# de0-nano_RMII.net
KiCad netlist of a schematic drawn in EAGLE
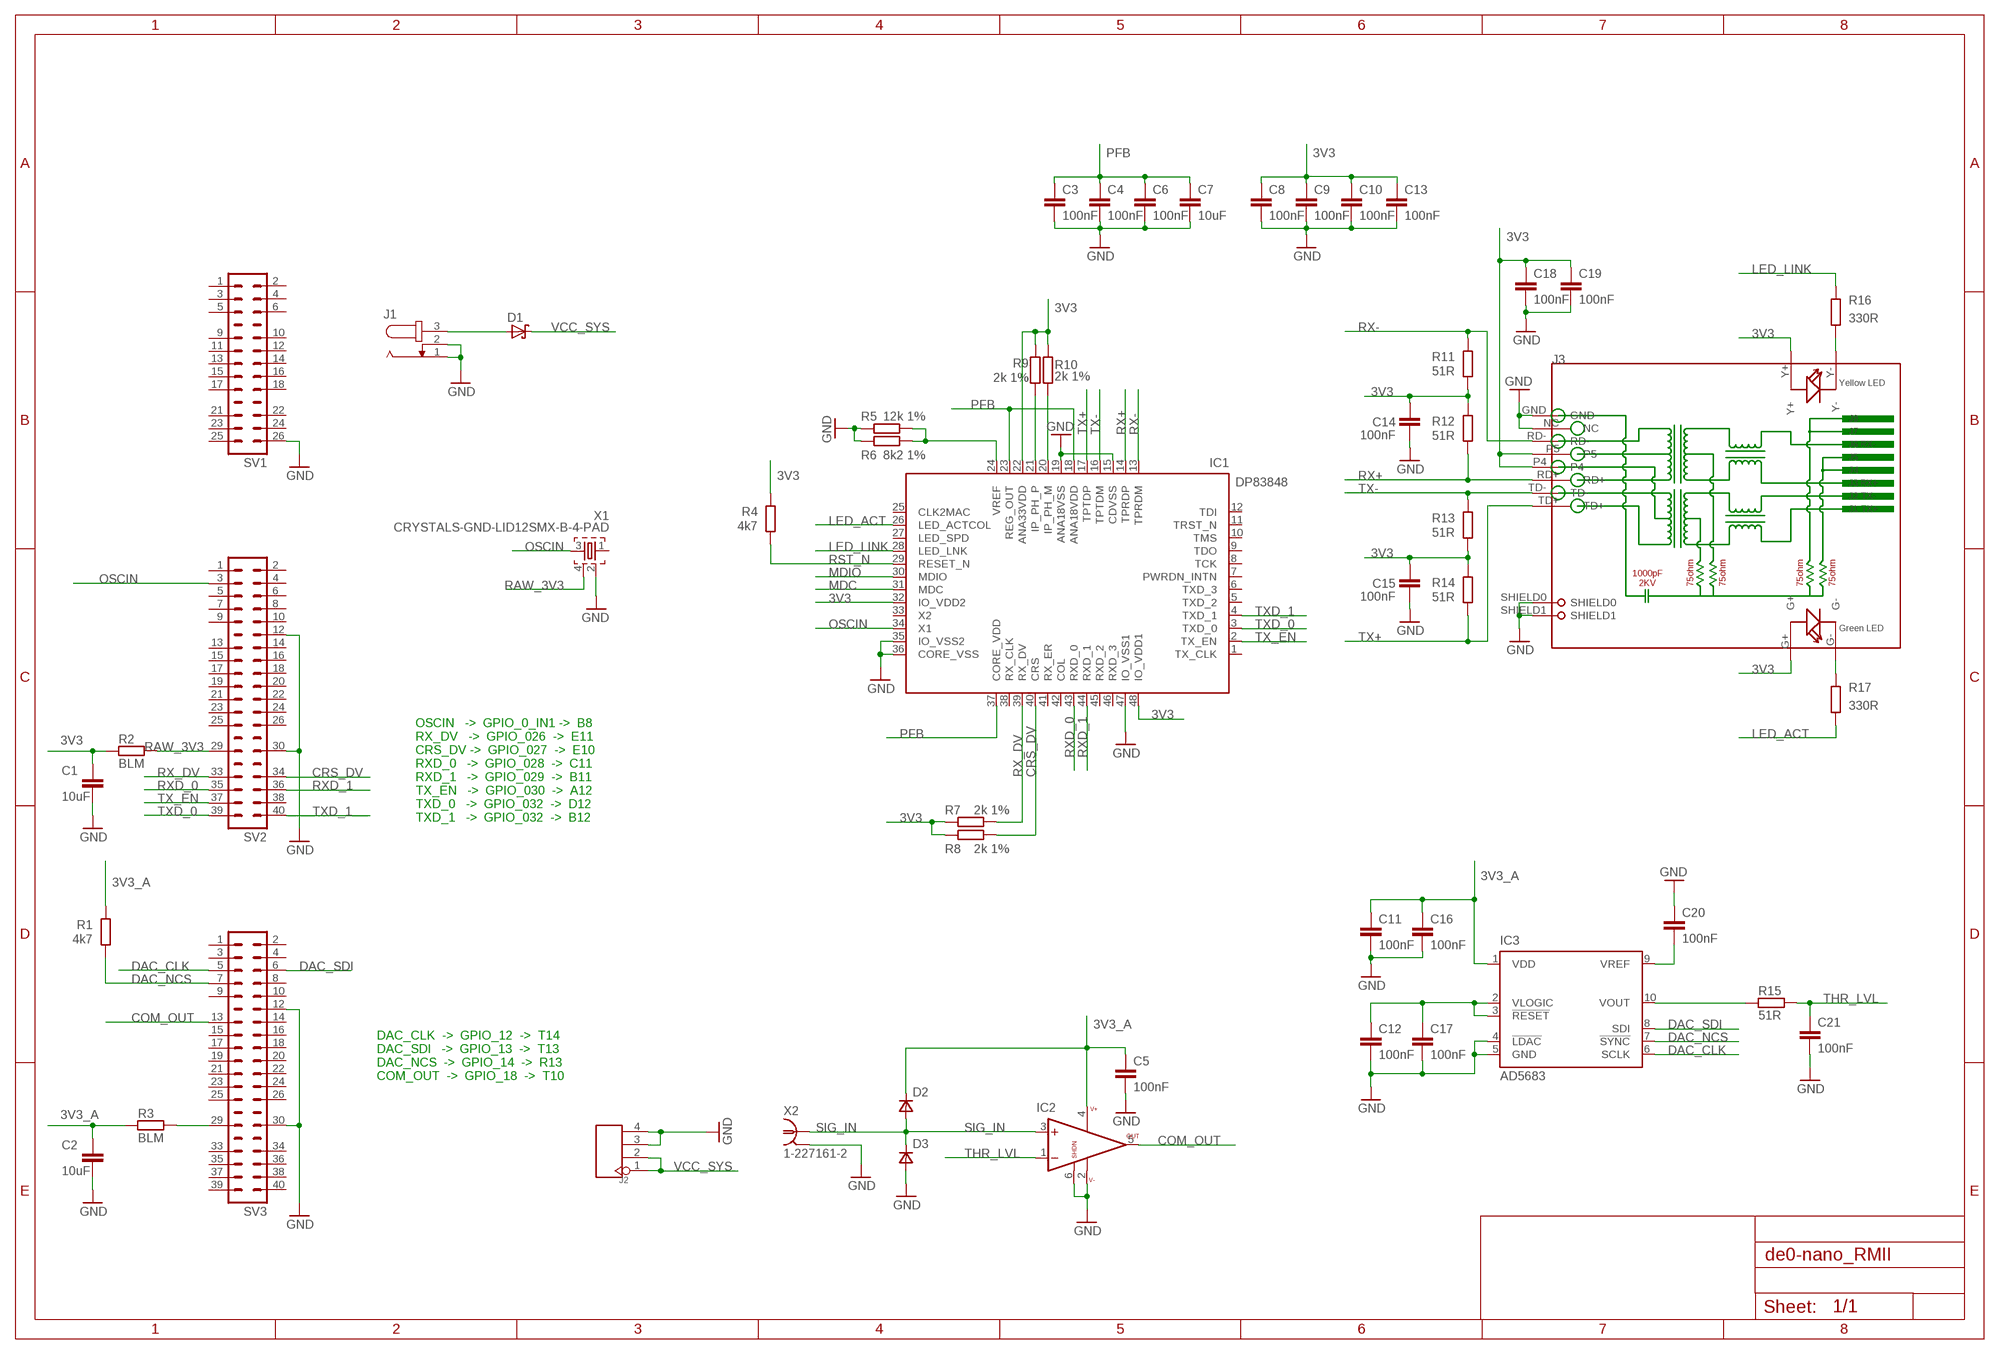
[diagram p0: schematic, sheet 1]

(export (version "E")
  (design (tool "Eeschema 10.0.6"))
  (components
    (comp (ref "C1")
      (value "10uF")
      (footprint "eagle-import:C0805")
      (libsource (lib "eagle-import") (part "C-EUC0805"))
    )
    (comp (ref "C2")
      (value "10uF")
      (footprint "eagle-import:C0805")
      (libsource (lib "eagle-import") (part "C-EUC0805"))
    )
    (comp (ref "C3")
      (value "100nF")
      (footprint "eagle-import:C0603")
      (libsource (lib "eagle-import") (part "C-EUC0603"))
    )
    (comp (ref "C4")
      (value "100nF")
      (footprint "eagle-import:C0603")
      (libsource (lib "eagle-import") (part "C-EUC0603"))
    )
    (comp (ref "C5")
      (value "100nF")
      (footprint "eagle-import:C0603")
      (libsource (lib "eagle-import") (part "C-EUC0603"))
    )
    (comp (ref "C6")
      (value "100nF")
      (footprint "eagle-import:C0603")
      (libsource (lib "eagle-import") (part "C-EUC0603"))
    )
    (comp (ref "C7")
      (value "10uF")
      (footprint "eagle-import:C0805")
      (libsource (lib "eagle-import") (part "C-EUC0805"))
    )
    (comp (ref "C8")
      (value "100nF")
      (footprint "eagle-import:C0603")
      (libsource (lib "eagle-import") (part "C-EUC0603"))
    )
    (comp (ref "C9")
      (value "100nF")
      (footprint "eagle-import:C0603")
      (libsource (lib "eagle-import") (part "C-EUC0603"))
    )
    (comp (ref "C10")
      (value "100nF")
      (footprint "eagle-import:C0603")
      (libsource (lib "eagle-import") (part "C-EUC0603"))
    )
    (comp (ref "C11")
      (value "100nF")
      (footprint "eagle-import:C0603")
      (libsource (lib "eagle-import") (part "C-EUC0603"))
    )
    (comp (ref "C12")
      (value "100nF")
      (footprint "eagle-import:C0603")
      (libsource (lib "eagle-import") (part "C-EUC0603"))
    )
    (comp (ref "C13")
      (value "100nF")
      (footprint "eagle-import:C0603")
      (libsource (lib "eagle-import") (part "C-EUC0603"))
    )
    (comp (ref "C14")
      (value "100nF")
      (footprint "eagle-import:C0603")
      (libsource (lib "eagle-import") (part "C-EUC0603"))
    )
    (comp (ref "C15")
      (value "100nF")
      (footprint "eagle-import:C0603")
      (libsource (lib "eagle-import") (part "C-EUC0603"))
    )
    (comp (ref "C16")
      (value "100nF")
      (footprint "eagle-import:C0603")
      (libsource (lib "eagle-import") (part "C-EUC0603"))
    )
    (comp (ref "C17")
      (value "100nF")
      (footprint "eagle-import:C0603")
      (libsource (lib "eagle-import") (part "C-EUC0603"))
    )
    (comp (ref "C18")
      (value "100nF")
      (footprint "eagle-import:C0603")
      (libsource (lib "eagle-import") (part "C-EUC0603"))
    )
    (comp (ref "C19")
      (value "100nF")
      (footprint "eagle-import:C0603")
      (libsource (lib "eagle-import") (part "C-EUC0603"))
    )
    (comp (ref "C20")
      (value "100nF")
      (footprint "eagle-import:C0603")
      (libsource (lib "eagle-import") (part "C-EUC0603"))
    )
    (comp (ref "C21")
      (value "100nF")
      (footprint "eagle-import:C0603")
      (libsource (lib "eagle-import") (part "C-EUC0603"))
    )
    (comp (ref "D1")
      (value "SCHOTTKY-DIODESMC")
      (footprint "eagle-import:SMC")
      (libsource (lib "eagle-import") (part "SCHOTTKY-DIODESMC"))
    )
    (comp (ref "D2")
      (value "DSOD323")
      (footprint "eagle-import:SOD323")
      (fields (field (name "MPN") "CDSOD323-T05C"))
      (libsource (lib "eagle-import") (part "DSOD323"))
    )
    (comp (ref "D3")
      (value "DSOD323")
      (footprint "eagle-import:SOD323")
      (fields (field (name "MPN") "CDSOD323-T05C"))
      (libsource (lib "eagle-import") (part "DSOD323"))
    )
    (comp (ref "IC1")
      (value "DP83848")
      (footprint "eagle-import:LQFP48")
      (fields (field (name "MPN") "DP83848VYB"))
      (libsource (lib "eagle-import") (part "DP83848"))
    )
    (comp (ref "IC2")
      (value "LT1719")
      (footprint "eagle-import:TSOT23-6")
      (libsource (lib "eagle-import") (part "LT1719"))
    )
    (comp (ref "IC3")
      (value "AD5683")
      (footprint "eagle-import:SO10")
      (fields (field (name "MPN") "SSM2167Z-EVAL"))
      (libsource (lib "eagle-import") (part "AD5683"))
    )
    (comp (ref "J1")
      (value "JACK-PLUG1")
      (footprint "eagle-import:SPC4078")
      (libsource (lib "eagle-import") (part "JACK-PLUG1"))
    )
    (comp (ref "J2")
      (value "HEADER-4P-60/35MIL")
      (footprint "eagle-import:4P-65_35MIL")
      (libsource (lib "eagle-import") (part "HEADER-4P-60/35MIL"))
    )
    (comp (ref "J3")
      (value "RJ45-HR911105A-HR911105A")
      (footprint "eagle-import:RJ45")
      (libsource (lib "eagle-import") (part "RJ45-HR911105A-HR911105A"))
    )
    (comp (ref "R1")
      (value "4k7")
      (footprint "eagle-import:R0603")
      (libsource (lib "eagle-import") (part "R-EU_R0603"))
    )
    (comp (ref "R2")
      (value "BLM")
      (footprint "eagle-import:R0603")
      (libsource (lib "eagle-import") (part "R-EU_R0603"))
    )
    (comp (ref "R3")
      (value "BLM")
      (footprint "eagle-import:R0603")
      (libsource (lib "eagle-import") (part "R-EU_R0603"))
    )
    (comp (ref "R4")
      (value "4k7")
      (footprint "eagle-import:R0603")
      (libsource (lib "eagle-import") (part "R-EU_R0603"))
    )
    (comp (ref "R5")
      (value "12k 1%")
      (footprint "eagle-import:R0603")
      (libsource (lib "eagle-import") (part "R-EU_R0603"))
    )
    (comp (ref "R6")
      (value "8k2 1%")
      (footprint "eagle-import:R0603")
      (libsource (lib "eagle-import") (part "R-EU_R0603"))
    )
    (comp (ref "R7")
      (value "2k 1%")
      (footprint "eagle-import:R0603")
      (libsource (lib "eagle-import") (part "R-EU_R0603"))
    )
    (comp (ref "R8")
      (value "2k 1%")
      (footprint "eagle-import:R0603")
      (libsource (lib "eagle-import") (part "R-EU_R0603"))
    )
    (comp (ref "R9")
      (value "2k 1%")
      (footprint "eagle-import:R0603")
      (libsource (lib "eagle-import") (part "R-EU_R0603"))
    )
    (comp (ref "R10")
      (value "2k 1%")
      (footprint "eagle-import:R0603")
      (libsource (lib "eagle-import") (part "R-EU_R0603"))
    )
    (comp (ref "R11")
      (value "51R")
      (footprint "eagle-import:R0603")
      (libsource (lib "eagle-import") (part "R-EU_R0603"))
    )
    (comp (ref "R12")
      (value "51R")
      (footprint "eagle-import:R0603")
      (libsource (lib "eagle-import") (part "R-EU_R0603"))
    )
    (comp (ref "R13")
      (value "51R")
      (footprint "eagle-import:R0603")
      (libsource (lib "eagle-import") (part "R-EU_R0603"))
    )
    (comp (ref "R14")
      (value "51R")
      (footprint "eagle-import:R0603")
      (libsource (lib "eagle-import") (part "R-EU_R0603"))
    )
    (comp (ref "R15")
      (value "51R")
      (footprint "eagle-import:R0603")
      (libsource (lib "eagle-import") (part "R-EU_R0603"))
    )
    (comp (ref "R16")
      (value "330R")
      (footprint "eagle-import:R0603")
      (libsource (lib "eagle-import") (part "R-EU_R0603"))
    )
    (comp (ref "R17")
      (value "330R")
      (footprint "eagle-import:R0603")
      (libsource (lib "eagle-import") (part "R-EU_R0603"))
    )
    (comp (ref "SV1")
      (value "MA13-2_ALT")
      (footprint "eagle-import:MA13-2_ALT")
      (libsource (lib "eagle-import") (part "MA13-2_ALT"))
    )
    (comp (ref "SV2")
      (value "MA20-2_ALT")
      (footprint "eagle-import:MA20-2_ALT")
      (libsource (lib "eagle-import") (part "MA20-2_ALT"))
    )
    (comp (ref "SV3")
      (value "MA20-2_ALT")
      (footprint "eagle-import:MA20-2_ALT")
      (libsource (lib "eagle-import") (part "MA20-2_ALT"))
    )
    (comp (ref "X1")
      (value "CRYSTALS-GND-LID12SMX-B-4-PAD")
      (footprint "eagle-import:7.5X5-4-PAD")
      (libsource (lib "eagle-import") (part "CRYSTALS-GND-LID-4-PAD12SMX-B"))
    )
    (comp (ref "X2")
      (value "1-227161-2")
      (footprint "eagle-import:AMP_227161")
      (libsource (lib "eagle-import") (part "?2271611--2"))
    )
  )
  (nets
    (net (code "1") (name "/3V3") (class "Default")
      (node (ref "C1") (pin "1") (pinfunction "1_1") (pintype "passive"))
      (node (ref "C10") (pin "1") (pinfunction "1_1") (pintype "passive"))
      (node (ref "C13") (pin "1") (pinfunction "1_1") (pintype "passive"))
      (node (ref "C14") (pin "1") (pinfunction "1_1") (pintype "passive"))
      (node (ref "C15") (pin "1") (pinfunction "1_1") (pintype "passive"))
      (node (ref "C18") (pin "1") (pinfunction "1_1") (pintype "passive"))
      (node (ref "C19") (pin "1") (pinfunction "1_1") (pintype "passive"))
      (node (ref "C8") (pin "1") (pinfunction "1_1") (pintype "passive"))
      (node (ref "C9") (pin "1") (pinfunction "1_1") (pintype "passive"))
      (node (ref "IC1") (pin "22") (pinfunction "ANA33VDD_22") (pintype "power_in"))
      (node (ref "IC1") (pin "32") (pinfunction "IO_VDD2_32") (pintype "power_in"))
      (node (ref "IC1") (pin "48") (pinfunction "IO_VDD1_48") (pintype "power_in"))
      (node (ref "J3") (pin "G+") (pinfunction "G+_G+") (pintype "bidirectional"))
      (node (ref "J3") (pin "P4") (pinfunction "P4_P4") (pintype "bidirectional"))
      (node (ref "J3") (pin "P5") (pinfunction "P5_P5") (pintype "bidirectional"))
      (node (ref "J3") (pin "Y+") (pinfunction "Y+_Y+") (pintype "bidirectional"))
      (node (ref "R10") (pin "2") (pinfunction "2_2") (pintype "passive"))
      (node (ref "R11") (pin "2") (pinfunction "2_2") (pintype "passive"))
      (node (ref "R12") (pin "1") (pinfunction "1_1") (pintype "passive"))
      (node (ref "R13") (pin "2") (pinfunction "2_2") (pintype "passive"))
      (node (ref "R14") (pin "1") (pinfunction "1_1") (pintype "passive"))
      (node (ref "R2") (pin "1") (pinfunction "1_1") (pintype "passive"))
      (node (ref "R4") (pin "1") (pinfunction "1_1") (pintype "passive"))
      (node (ref "R7") (pin "2") (pinfunction "2_2") (pintype "passive"))
      (node (ref "R8") (pin "2") (pinfunction "2_2") (pintype "passive"))
      (node (ref "R9") (pin "2") (pinfunction "2_2") (pintype "passive"))
    )
    (net (code "2") (name "/3V3_A") (class "Default")
      (node (ref "C11") (pin "1") (pinfunction "1_1") (pintype "passive"))
      (node (ref "C16") (pin "1") (pinfunction "1_1") (pintype "passive"))
      (node (ref "C2") (pin "1") (pinfunction "1_1") (pintype "passive"))
      (node (ref "C5") (pin "1") (pinfunction "1_1") (pintype "passive"))
      (node (ref "D2") (pin "1") (pinfunction "C_1") (pintype "passive"))
      (node (ref "IC2") (pin "4") (pinfunction "V+_4") (pintype "power_in"))
      (node (ref "IC3") (pin "1") (pinfunction "VDD_1") (pintype "power_in"))
      (node (ref "R1") (pin "1") (pinfunction "1_1") (pintype "passive"))
      (node (ref "R3") (pin "1") (pinfunction "1_1") (pintype "passive"))
    )
    (net (code "3") (name "/COM_OUT") (class "Default")
      (node (ref "IC2") (pin "5") (pinfunction "OUT_5") (pintype "output"))
      (node (ref "SV3") (pin "13") (pinfunction "13_13") (pintype "passive"))
    )
    (net (code "4") (name "/CRS_DV") (class "Default")
      (node (ref "IC1") (pin "40") (pinfunction "CRS_40") (pintype "bidirectional"))
      (node (ref "R8") (pin "1") (pinfunction "1_1") (pintype "passive"))
      (node (ref "SV2") (pin "34") (pinfunction "34_34") (pintype "passive"))
    )
    (net (code "5") (name "/DAC_CLK") (class "Default")
      (node (ref "IC3") (pin "6") (pinfunction "SCLK_6") (pintype "passive"))
      (node (ref "SV3") (pin "5") (pinfunction "5_5") (pintype "passive"))
    )
    (net (code "6") (name "/DAC_NCS") (class "Default")
      (node (ref "IC3") (pin "7") (pinfunction "~{SYNC}_7") (pintype "passive"))
      (node (ref "R1") (pin "2") (pinfunction "2_2") (pintype "passive"))
      (node (ref "SV3") (pin "7") (pinfunction "7_7") (pintype "passive"))
    )
    (net (code "7") (name "/DAC_SDI") (class "Default")
      (node (ref "IC3") (pin "8") (pinfunction "SDI_8") (pintype "passive"))
      (node (ref "SV3") (pin "6") (pinfunction "6_6") (pintype "passive"))
    )
    (net (code "8") (name "/LED_ACT") (class "Default")
      (node (ref "IC1") (pin "26") (pinfunction "LED_ACTCOL_26") (pintype "bidirectional"))
      (node (ref "R17") (pin "1") (pinfunction "1_1") (pintype "passive"))
    )
    (net (code "9") (name "/LED_LINK") (class "Default")
      (node (ref "IC1") (pin "28") (pinfunction "LED_LNK_28") (pintype "bidirectional"))
      (node (ref "R16") (pin "2") (pinfunction "2_2") (pintype "passive"))
    )
    (net (code "10") (name "/MDC") (class "Default")
      (node (ref "IC1") (pin "31") (pinfunction "MDC_31") (pintype "input"))
    )
    (net (code "11") (name "/MDIO") (class "Default")
      (node (ref "IC1") (pin "30") (pinfunction "MDIO_30") (pintype "bidirectional"))
    )
    (net (code "12") (name "/OSCIN") (class "Default")
      (node (ref "IC1") (pin "34") (pinfunction "X1_34") (pintype "input"))
      (node (ref "SV2") (pin "3") (pinfunction "3_3") (pintype "passive"))
      (node (ref "X1") (pin "3") (pinfunction "3_3") (pintype "passive"))
    )
    (net (code "13") (name "/PFB") (class "Default")
      (node (ref "C3") (pin "1") (pinfunction "1_1") (pintype "passive"))
      (node (ref "C4") (pin "1") (pinfunction "1_1") (pintype "passive"))
      (node (ref "C6") (pin "1") (pinfunction "1_1") (pintype "passive"))
      (node (ref "C7") (pin "1") (pinfunction "1_1") (pintype "passive"))
      (node (ref "IC1") (pin "18") (pinfunction "ANA18VDD_18") (pintype "power_in"))
      (node (ref "IC1") (pin "23") (pinfunction "REG_OUT_23") (pintype "output"))
      (node (ref "IC1") (pin "37") (pinfunction "CORE_VDD_37") (pintype "power_in"))
    )
    (net (code "14") (name "/RAW_3V3") (class "Default")
      (node (ref "R2") (pin "2") (pinfunction "2_2") (pintype "passive"))
      (node (ref "SV2") (pin "29") (pinfunction "29_29") (pintype "passive"))
      (node (ref "X1") (pin "4") (pinfunction "4_4") (pintype "passive"))
    )
    (net (code "15") (name "/RST_N") (class "Default")
      (node (ref "IC1") (pin "29") (pinfunction "RESET_N_29") (pintype "input"))
      (node (ref "R4") (pin "2") (pinfunction "2_2") (pintype "passive"))
    )
    (net (code "16") (name "/RX+") (class "Default")
      (node (ref "IC1") (pin "14") (pinfunction "TPRDP_14") (pintype "bidirectional"))
      (node (ref "J3") (pin "RD+") (pinfunction "RD+_RD+") (pintype "bidirectional"))
      (node (ref "R12") (pin "2") (pinfunction "2_2") (pintype "passive"))
    )
    (net (code "17") (name "/RX-") (class "Default")
      (node (ref "IC1") (pin "13") (pinfunction "TPRDM_13") (pintype "bidirectional"))
      (node (ref "J3") (pin "RD-") (pinfunction "RD-_RD-") (pintype "bidirectional"))
      (node (ref "R11") (pin "1") (pinfunction "1_1") (pintype "passive"))
    )
    (net (code "18") (name "/RXD_0") (class "Default")
      (node (ref "IC1") (pin "43") (pinfunction "RXD_0_43") (pintype "bidirectional"))
      (node (ref "SV2") (pin "35") (pinfunction "35_35") (pintype "passive"))
    )
    (net (code "19") (name "/RXD_1") (class "Default")
      (node (ref "IC1") (pin "44") (pinfunction "RXD_1_44") (pintype "bidirectional"))
      (node (ref "SV2") (pin "36") (pinfunction "36_36") (pintype "passive"))
    )
    (net (code "20") (name "/RX_DV") (class "Default")
      (node (ref "IC1") (pin "39") (pinfunction "RX_DV_39") (pintype "bidirectional"))
      (node (ref "R7") (pin "1") (pinfunction "1_1") (pintype "passive"))
      (node (ref "SV2") (pin "33") (pinfunction "33_33") (pintype "passive"))
    )
    (net (code "21") (name "/SIG_IN") (class "Default")
      (node (ref "D2") (pin "2") (pinfunction "A_2") (pintype "passive"))
      (node (ref "D3") (pin "1") (pinfunction "C_1") (pintype "passive"))
      (node (ref "IC2") (pin "3") (pinfunction "+IN_3") (pintype "input"))
      (node (ref "X2") (pin "1") (pinfunction "1_1") (pintype "passive"))
    )
    (net (code "22") (name "/THR_LVL") (class "Default")
      (node (ref "C21") (pin "1") (pinfunction "1_1") (pintype "passive"))
      (node (ref "IC2") (pin "1") (pinfunction "-IN_1") (pintype "input"))
      (node (ref "R15") (pin "2") (pinfunction "2_2") (pintype "passive"))
    )
    (net (code "23") (name "/TX+") (class "Default")
      (node (ref "IC1") (pin "17") (pinfunction "TPTDP_17") (pintype "bidirectional"))
      (node (ref "J3") (pin "TD+") (pinfunction "TD+_TD+") (pintype "bidirectional"))
      (node (ref "R14") (pin "2") (pinfunction "2_2") (pintype "passive"))
    )
    (net (code "24") (name "/TX-") (class "Default")
      (node (ref "IC1") (pin "16") (pinfunction "TPTDM_16") (pintype "bidirectional"))
      (node (ref "J3") (pin "TD-") (pinfunction "TD-_TD-") (pintype "bidirectional"))
      (node (ref "R13") (pin "1") (pinfunction "1_1") (pintype "passive"))
    )
    (net (code "25") (name "/TXD_0") (class "Default")
      (node (ref "IC1") (pin "3") (pinfunction "TXD_0_3") (pintype "bidirectional"))
      (node (ref "SV2") (pin "39") (pinfunction "39_39") (pintype "passive"))
    )
    (net (code "26") (name "/TXD_1") (class "Default")
      (node (ref "IC1") (pin "4") (pinfunction "TXD_1_4") (pintype "bidirectional"))
      (node (ref "SV2") (pin "40") (pinfunction "40_40") (pintype "passive"))
    )
    (net (code "27") (name "/TX_EN") (class "Default")
      (node (ref "IC1") (pin "2") (pinfunction "TX_EN_2") (pintype "bidirectional"))
      (node (ref "SV2") (pin "37") (pinfunction "37_37") (pintype "passive"))
    )
    (net (code "28") (name "/VCC_SYS") (class "Default")
      (node (ref "D1") (pin "C") (pinfunction "C_C") (pintype "passive"))
      (node (ref "J2") (pin "1") (pinfunction "P$1_1") (pintype "bidirectional"))
      (node (ref "J2") (pin "2") (pinfunction "P$2_2") (pintype "bidirectional"))
    )
    (net (code "29") (name "GND") (class "Default")
      (node (ref "C1") (pin "2") (pinfunction "2_2") (pintype "passive"))
      (node (ref "C10") (pin "2") (pinfunction "2_2") (pintype "passive"))
      (node (ref "C11") (pin "2") (pinfunction "2_2") (pintype "passive"))
      (node (ref "C12") (pin "2") (pinfunction "2_2") (pintype "passive"))
      (node (ref "C13") (pin "2") (pinfunction "2_2") (pintype "passive"))
      (node (ref "C14") (pin "2") (pinfunction "2_2") (pintype "passive"))
      (node (ref "C15") (pin "2") (pinfunction "2_2") (pintype "passive"))
      (node (ref "C16") (pin "2") (pinfunction "2_2") (pintype "passive"))
      (node (ref "C17") (pin "2") (pinfunction "2_2") (pintype "passive"))
      (node (ref "C18") (pin "2") (pinfunction "2_2") (pintype "passive"))
      (node (ref "C19") (pin "2") (pinfunction "2_2") (pintype "passive"))
      (node (ref "C2") (pin "2") (pinfunction "2_2") (pintype "passive"))
      (node (ref "C20") (pin "2") (pinfunction "2_2") (pintype "passive"))
      (node (ref "C21") (pin "2") (pinfunction "2_2") (pintype "passive"))
      (node (ref "C3") (pin "2") (pinfunction "2_2") (pintype "passive"))
      (node (ref "C4") (pin "2") (pinfunction "2_2") (pintype "passive"))
      (node (ref "C5") (pin "2") (pinfunction "2_2") (pintype "passive"))
      (node (ref "C6") (pin "2") (pinfunction "2_2") (pintype "passive"))
      (node (ref "C7") (pin "2") (pinfunction "2_2") (pintype "passive"))
      (node (ref "C8") (pin "2") (pinfunction "2_2") (pintype "passive"))
      (node (ref "C9") (pin "2") (pinfunction "2_2") (pintype "passive"))
      (node (ref "D3") (pin "2") (pinfunction "A_2") (pintype "passive"))
      (node (ref "IC1") (pin "15") (pinfunction "CDVSS_15") (pintype "power_in"))
      (node (ref "IC1") (pin "19") (pinfunction "ANA18VSS_19") (pintype "power_in"))
      (node (ref "IC1") (pin "35") (pinfunction "IO_VSS2_35") (pintype "power_in"))
      (node (ref "IC1") (pin "36") (pinfunction "CORE_VSS_36") (pintype "power_in"))
      (node (ref "IC1") (pin "47") (pinfunction "IO_VSS1_47") (pintype "power_in"))
      (node (ref "IC2") (pin "2") (pinfunction "V-_2") (pintype "power_in"))
      (node (ref "IC2") (pin "6") (pinfunction "SHDN_6") (pintype "input"))
      (node (ref "IC3") (pin "4") (pinfunction "~{LDAC}_4") (pintype "output"))
      (node (ref "IC3") (pin "5") (pinfunction "GND_5") (pintype "power_in"))
      (node (ref "J1") (pin "1") (pinfunction "1_1") (pintype "passive"))
      (node (ref "J1") (pin "2") (pinfunction "2_2") (pintype "passive"))
      (node (ref "J2") (pin "3") (pinfunction "P$3_3") (pintype "bidirectional"))
      (node (ref "J2") (pin "4") (pinfunction "P$4_4") (pintype "bidirectional"))
      (node (ref "J3") (pin "GND") (pinfunction "GND_GND") (pintype "bidirectional"))
      (node (ref "J3") (pin "NC") (pinfunction "NC_NC") (pintype "bidirectional"))
      (node (ref "J3") (pin "SHIELD0") (pinfunction "SHIELD0_SHIELD0") (pintype "bidirectional"))
      (node (ref "J3") (pin "SHIELD1") (pinfunction "SHIELD1_SHIELD1") (pintype "bidirectional"))
      (node (ref "R5") (pin "2") (pinfunction "2_2") (pintype "passive"))
      (node (ref "R6") (pin "2") (pinfunction "2_2") (pintype "passive"))
      (node (ref "SV1") (pin "26") (pinfunction "26_26") (pintype "passive"))
      (node (ref "SV2") (pin "12") (pinfunction "12_12") (pintype "passive"))
      (node (ref "SV2") (pin "30") (pinfunction "30_30") (pintype "passive"))
      (node (ref "SV3") (pin "12") (pinfunction "12_12") (pintype "passive"))
      (node (ref "SV3") (pin "30") (pinfunction "30_30") (pintype "passive"))
      (node (ref "X1") (pin "2") (pinfunction "2_2") (pintype "passive"))
      (node (ref "X2") (pin "2") (pinfunction "2_2") (pintype "passive"))
    )
    (net (code "30") (name "Net-(D1-PadA)") (class "Default")
      (node (ref "D1") (pin "A") (pinfunction "A_A") (pintype "passive"))
      (node (ref "J1") (pin "3") (pinfunction "3_3") (pintype "passive"))
    )
    (net (code "31") (name "Net-(IC1-IP_PH_M)") (class "Default")
      (node (ref "IC1") (pin "20") (pinfunction "IP_PH_M_20") (pintype "input"))
      (node (ref "R10") (pin "1") (pinfunction "1_1") (pintype "passive"))
    )
    (net (code "32") (name "Net-(IC1-IP_PH_P)") (class "Default")
      (node (ref "IC1") (pin "21") (pinfunction "IP_PH_P_21") (pintype "input"))
      (node (ref "R9") (pin "1") (pinfunction "1_1") (pintype "passive"))
    )
    (net (code "33") (name "Net-(IC1-VREF)") (class "Default")
      (node (ref "IC1") (pin "24") (pinfunction "VREF_24") (pintype "bidirectional"))
      (node (ref "R5") (pin "1") (pinfunction "1_1") (pintype "passive"))
      (node (ref "R6") (pin "1") (pinfunction "1_1") (pintype "passive"))
    )
    (net (code "34") (name "Net-(IC3-VLOGIC)") (class "Default")
      (node (ref "C12") (pin "1") (pinfunction "1_1") (pintype "passive"))
      (node (ref "C17") (pin "1") (pinfunction "1_1") (pintype "passive"))
      (node (ref "IC3") (pin "2") (pinfunction "VLOGIC_2") (pintype "bidirectional"))
      (node (ref "IC3") (pin "3") (pinfunction "~{RESET}_3") (pintype "bidirectional"))
    )
    (net (code "35") (name "Net-(IC3-VOUT)") (class "Default")
      (node (ref "IC3") (pin "10") (pinfunction "VOUT_10") (pintype "output"))
      (node (ref "R15") (pin "1") (pinfunction "1_1") (pintype "passive"))
    )
    (net (code "36") (name "Net-(IC3-VREF)") (class "Default")
      (node (ref "C20") (pin "1") (pinfunction "1_1") (pintype "passive"))
      (node (ref "IC3") (pin "9") (pinfunction "VREF_9") (pintype "input"))
    )
    (net (code "37") (name "Net-(J3-PadG-)") (class "Default")
      (node (ref "J3") (pin "G-") (pinfunction "G-_G-") (pintype "bidirectional"))
      (node (ref "R17") (pin "2") (pinfunction "2_2") (pintype "passive"))
    )
    (net (code "38") (name "Net-(J3-PadY-)") (class "Default")
      (node (ref "J3") (pin "Y-") (pinfunction "Y-_Y-") (pintype "bidirectional"))
      (node (ref "R16") (pin "1") (pinfunction "1_1") (pintype "passive"))
    )
    (net (code "39") (name "Net-(R3-Pad2)") (class "Default")
      (node (ref "R3") (pin "2") (pinfunction "2_2") (pintype "passive"))
      (node (ref "SV3") (pin "29") (pinfunction "29_29") (pintype "passive"))
    )
    (net (code "40") (name "unconnected-(IC1-CLK2MAC-Pad25)") (class "Default")
      (node (ref "IC1") (pin "25") (pinfunction "CLK2MAC_25") (pintype "bidirectional"))
    )
    (net (code "41") (name "unconnected-(IC1-COL-Pad42)") (class "Default")
      (node (ref "IC1") (pin "42") (pinfunction "COL_42") (pintype "bidirectional"))
    )
    (net (code "42") (name "unconnected-(IC1-LED_SPD-Pad27)") (class "Default")
      (node (ref "IC1") (pin "27") (pinfunction "LED_SPD_27") (pintype "bidirectional"))
    )
    (net (code "43") (name "unconnected-(IC1-PWRDN_INTN-Pad7)") (class "Default")
      (node (ref "IC1") (pin "7") (pinfunction "PWRDN_INTN_7") (pintype "bidirectional"))
    )
    (net (code "44") (name "unconnected-(IC1-RXD_2-Pad45)") (class "Default")
      (node (ref "IC1") (pin "45") (pinfunction "RXD_2_45") (pintype "bidirectional"))
    )
    (net (code "45") (name "unconnected-(IC1-RXD_3-Pad46)") (class "Default")
      (node (ref "IC1") (pin "46") (pinfunction "RXD_3_46") (pintype "bidirectional"))
    )
    (net (code "46") (name "unconnected-(IC1-RX_CLK-Pad38)") (class "Default")
      (node (ref "IC1") (pin "38") (pinfunction "RX_CLK_38") (pintype "bidirectional"))
    )
    (net (code "47") (name "unconnected-(IC1-RX_ER-Pad41)") (class "Default")
      (node (ref "IC1") (pin "41") (pinfunction "RX_ER_41") (pintype "bidirectional"))
    )
    (net (code "48") (name "unconnected-(IC1-TCK-Pad8)") (class "Default")
      (node (ref "IC1") (pin "8") (pinfunction "TCK_8") (pintype "input"))
    )
    (net (code "49") (name "unconnected-(IC1-TDI-Pad12)") (class "Default")
      (node (ref "IC1") (pin "12") (pinfunction "TDI_12") (pintype "input"))
    )
    (net (code "50") (name "unconnected-(IC1-TDO-Pad9)") (class "Default")
      (node (ref "IC1") (pin "9") (pinfunction "TDO_9") (pintype "output"))
    )
    (net (code "51") (name "unconnected-(IC1-TMS-Pad10)") (class "Default")
      (node (ref "IC1") (pin "10") (pinfunction "TMS_10") (pintype "input"))
    )
    (net (code "52") (name "unconnected-(IC1-TRST_N-Pad11)") (class "Default")
      (node (ref "IC1") (pin "11") (pinfunction "TRST_N_11") (pintype "input"))
    )
    (net (code "53") (name "unconnected-(IC1-TXD_2-Pad5)") (class "Default")
      (node (ref "IC1") (pin "5") (pinfunction "TXD_2_5") (pintype "bidirectional"))
    )
    (net (code "54") (name "unconnected-(IC1-TXD_3-Pad6)") (class "Default")
      (node (ref "IC1") (pin "6") (pinfunction "TXD_3_6") (pintype "bidirectional"))
    )
    (net (code "55") (name "unconnected-(IC1-TX_CLK-Pad1)") (class "Default")
      (node (ref "IC1") (pin "1") (pinfunction "TX_CLK_1") (pintype "bidirectional"))
    )
    (net (code "56") (name "unconnected-(IC1-X2-Pad33)") (class "Default")
      (node (ref "IC1") (pin "33") (pinfunction "X2_33") (pintype "output"))
    )
    (net (code "57") (name "unconnected-(SV1-Pad1)") (class "Default")
      (node (ref "SV1") (pin "1") (pinfunction "1_1") (pintype "passive"))
    )
    (net (code "58") (name "unconnected-(SV1-Pad2)") (class "Default")
      (node (ref "SV1") (pin "2") (pinfunction "2_2") (pintype "passive"))
    )
    (net (code "59") (name "unconnected-(SV1-Pad3)") (class "Default")
      (node (ref "SV1") (pin "3") (pinfunction "3_3") (pintype "passive"))
    )
    (net (code "60") (name "unconnected-(SV1-Pad4)") (class "Default")
      (node (ref "SV1") (pin "4") (pinfunction "4_4") (pintype "passive"))
    )
    (net (code "61") (name "unconnected-(SV1-Pad5)") (class "Default")
      (node (ref "SV1") (pin "5") (pinfunction "5_5") (pintype "passive"))
    )
    (net (code "62") (name "unconnected-(SV1-Pad6)") (class "Default")
      (node (ref "SV1") (pin "6") (pinfunction "6_6") (pintype "passive"))
    )
    (net (code "63") (name "unconnected-(SV1-Pad9)") (class "Default")
      (node (ref "SV1") (pin "9") (pinfunction "9_9") (pintype "passive"))
    )
    (net (code "64") (name "unconnected-(SV1-Pad10)") (class "Default")
      (node (ref "SV1") (pin "10") (pinfunction "10_10") (pintype "passive"))
    )
    (net (code "65") (name "unconnected-(SV1-Pad11)") (class "Default")
      (node (ref "SV1") (pin "11") (pinfunction "11_11") (pintype "passive"))
    )
    (net (code "66") (name "unconnected-(SV1-Pad12)") (class "Default")
      (node (ref "SV1") (pin "12") (pinfunction "12_12") (pintype "passive"))
    )
    (net (code "67") (name "unconnected-(SV1-Pad13)") (class "Default")
      (node (ref "SV1") (pin "13") (pinfunction "13_13") (pintype "passive"))
    )
    (net (code "68") (name "unconnected-(SV1-Pad14)") (class "Default")
      (node (ref "SV1") (pin "14") (pinfunction "14_14") (pintype "passive"))
    )
    (net (code "69") (name "unconnected-(SV1-Pad15)") (class "Default")
      (node (ref "SV1") (pin "15") (pinfunction "15_15") (pintype "passive"))
    )
    (net (code "70") (name "unconnected-(SV1-Pad16)") (class "Default")
      (node (ref "SV1") (pin "16") (pinfunction "16_16") (pintype "passive"))
    )
    (net (code "71") (name "unconnected-(SV1-Pad17)") (class "Default")
      (node (ref "SV1") (pin "17") (pinfunction "17_17") (pintype "passive"))
    )
    (net (code "72") (name "unconnected-(SV1-Pad18)") (class "Default")
      (node (ref "SV1") (pin "18") (pinfunction "18_18") (pintype "passive"))
    )
    (net (code "73") (name "unconnected-(SV1-Pad21)") (class "Default")
      (node (ref "SV1") (pin "21") (pinfunction "21_21") (pintype "passive"))
    )
    (net (code "74") (name "unconnected-(SV1-Pad22)") (class "Default")
      (node (ref "SV1") (pin "22") (pinfunction "22_22") (pintype "passive"))
    )
    (net (code "75") (name "unconnected-(SV1-Pad23)") (class "Default")
      (node (ref "SV1") (pin "23") (pinfunction "23_23") (pintype "passive"))
    )
    (net (code "76") (name "unconnected-(SV1-Pad24)") (class "Default")
      (node (ref "SV1") (pin "24") (pinfunction "24_24") (pintype "passive"))
    )
    (net (code "77") (name "unconnected-(SV1-Pad25)") (class "Default")
      (node (ref "SV1") (pin "25") (pinfunction "25_25") (pintype "passive"))
    )
    (net (code "78") (name "unconnected-(SV2-Pad1)") (class "Default")
      (node (ref "SV2") (pin "1") (pinfunction "1_1") (pintype "passive"))
    )
    (net (code "79") (name "unconnected-(SV2-Pad2)") (class "Default")
      (node (ref "SV2") (pin "2") (pinfunction "2_2") (pintype "passive"))
    )
    (net (code "80") (name "unconnected-(SV2-Pad4)") (class "Default")
      (node (ref "SV2") (pin "4") (pinfunction "4_4") (pintype "passive"))
    )
    (net (code "81") (name "unconnected-(SV2-Pad5)") (class "Default")
      (node (ref "SV2") (pin "5") (pinfunction "5_5") (pintype "passive"))
    )
    (net (code "82") (name "unconnected-(SV2-Pad6)") (class "Default")
      (node (ref "SV2") (pin "6") (pinfunction "6_6") (pintype "passive"))
    )
    (net (code "83") (name "unconnected-(SV2-Pad7)") (class "Default")
      (node (ref "SV2") (pin "7") (pinfunction "7_7") (pintype "passive"))
    )
    (net (code "84") (name "unconnected-(SV2-Pad8)") (class "Default")
      (node (ref "SV2") (pin "8") (pinfunction "8_8") (pintype "passive"))
    )
    (net (code "85") (name "unconnected-(SV2-Pad9)") (class "Default")
      (node (ref "SV2") (pin "9") (pinfunction "9_9") (pintype "passive"))
    )
    (net (code "86") (name "unconnected-(SV2-Pad10)") (class "Default")
      (node (ref "SV2") (pin "10") (pinfunction "10_10") (pintype "passive"))
    )
    (net (code "87") (name "unconnected-(SV2-Pad13)") (class "Default")
      (node (ref "SV2") (pin "13") (pinfunction "13_13") (pintype "passive"))
    )
    (net (code "88") (name "unconnected-(SV2-Pad14)") (class "Default")
      (node (ref "SV2") (pin "14") (pinfunction "14_14") (pintype "passive"))
    )
    (net (code "89") (name "unconnected-(SV2-Pad15)") (class "Default")
      (node (ref "SV2") (pin "15") (pinfunction "15_15") (pintype "passive"))
    )
    (net (code "90") (name "unconnected-(SV2-Pad16)") (class "Default")
      (node (ref "SV2") (pin "16") (pinfunction "16_16") (pintype "passive"))
    )
    (net (code "91") (name "unconnected-(SV2-Pad17)") (class "Default")
      (node (ref "SV2") (pin "17") (pinfunction "17_17") (pintype "passive"))
    )
    (net (code "92") (name "unconnected-(SV2-Pad18)") (class "Default")
      (node (ref "SV2") (pin "18") (pinfunction "18_18") (pintype "passive"))
    )
    (net (code "93") (name "unconnected-(SV2-Pad19)") (class "Default")
      (node (ref "SV2") (pin "19") (pinfunction "19_19") (pintype "passive"))
    )
    (net (code "94") (name "unconnected-(SV2-Pad20)") (class "Default")
      (node (ref "SV2") (pin "20") (pinfunction "20_20") (pintype "passive"))
    )
    (net (code "95") (name "unconnected-(SV2-Pad21)") (class "Default")
      (node (ref "SV2") (pin "21") (pinfunction "21_21") (pintype "passive"))
    )
    (net (code "96") (name "unconnected-(SV2-Pad22)") (class "Default")
      (node (ref "SV2") (pin "22") (pinfunction "22_22") (pintype "passive"))
    )
    (net (code "97") (name "unconnected-(SV2-Pad23)") (class "Default")
      (node (ref "SV2") (pin "23") (pinfunction "23_23") (pintype "passive"))
    )
    (net (code "98") (name "unconnected-(SV2-Pad24)") (class "Default")
      (node (ref "SV2") (pin "24") (pinfunction "24_24") (pintype "passive"))
    )
    (net (code "99") (name "unconnected-(SV2-Pad25)") (class "Default")
      (node (ref "SV2") (pin "25") (pinfunction "25_25") (pintype "passive"))
    )
    (net (code "100") (name "unconnected-(SV2-Pad26)") (class "Default")
      (node (ref "SV2") (pin "26") (pinfunction "26_26") (pintype "passive"))
    )
    (net (code "101") (name "unconnected-(SV2-Pad38)") (class "Default")
      (node (ref "SV2") (pin "38") (pinfunction "38_38") (pintype "passive"))
    )
    (net (code "102") (name "unconnected-(SV3-Pad1)") (class "Default")
      (node (ref "SV3") (pin "1") (pinfunction "1_1") (pintype "passive"))
    )
    (net (code "103") (name "unconnected-(SV3-Pad2)") (class "Default")
      (node (ref "SV3") (pin "2") (pinfunction "2_2") (pintype "passive"))
    )
    (net (code "104") (name "unconnected-(SV3-Pad3)") (class "Default")
      (node (ref "SV3") (pin "3") (pinfunction "3_3") (pintype "passive"))
    )
    (net (code "105") (name "unconnected-(SV3-Pad4)") (class "Default")
      (node (ref "SV3") (pin "4") (pinfunction "4_4") (pintype "passive"))
    )
    (net (code "106") (name "unconnected-(SV3-Pad8)") (class "Default")
      (node (ref "SV3") (pin "8") (pinfunction "8_8") (pintype "passive"))
    )
    (net (code "107") (name "unconnected-(SV3-Pad9)") (class "Default")
      (node (ref "SV3") (pin "9") (pinfunction "9_9") (pintype "passive"))
    )
    (net (code "108") (name "unconnected-(SV3-Pad10)") (class "Default")
      (node (ref "SV3") (pin "10") (pinfunction "10_10") (pintype "passive"))
    )
    (net (code "109") (name "unconnected-(SV3-Pad14)") (class "Default")
      (node (ref "SV3") (pin "14") (pinfunction "14_14") (pintype "passive"))
    )
    (net (code "110") (name "unconnected-(SV3-Pad15)") (class "Default")
      (node (ref "SV3") (pin "15") (pinfunction "15_15") (pintype "passive"))
    )
    (net (code "111") (name "unconnected-(SV3-Pad16)") (class "Default")
      (node (ref "SV3") (pin "16") (pinfunction "16_16") (pintype "passive"))
    )
    (net (code "112") (name "unconnected-(SV3-Pad17)") (class "Default")
      (node (ref "SV3") (pin "17") (pinfunction "17_17") (pintype "passive"))
    )
    (net (code "113") (name "unconnected-(SV3-Pad18)") (class "Default")
      (node (ref "SV3") (pin "18") (pinfunction "18_18") (pintype "passive"))
    )
    (net (code "114") (name "unconnected-(SV3-Pad19)") (class "Default")
      (node (ref "SV3") (pin "19") (pinfunction "19_19") (pintype "passive"))
    )
    (net (code "115") (name "unconnected-(SV3-Pad20)") (class "Default")
      (node (ref "SV3") (pin "20") (pinfunction "20_20") (pintype "passive"))
    )
    (net (code "116") (name "unconnected-(SV3-Pad21)") (class "Default")
      (node (ref "SV3") (pin "21") (pinfunction "21_21") (pintype "passive"))
    )
    (net (code "117") (name "unconnected-(SV3-Pad22)") (class "Default")
      (node (ref "SV3") (pin "22") (pinfunction "22_22") (pintype "passive"))
    )
    (net (code "118") (name "unconnected-(SV3-Pad23)") (class "Default")
      (node (ref "SV3") (pin "23") (pinfunction "23_23") (pintype "passive"))
    )
    (net (code "119") (name "unconnected-(SV3-Pad24)") (class "Default")
      (node (ref "SV3") (pin "24") (pinfunction "24_24") (pintype "passive"))
    )
    (net (code "120") (name "unconnected-(SV3-Pad25)") (class "Default")
      (node (ref "SV3") (pin "25") (pinfunction "25_25") (pintype "passive"))
    )
    (net (code "121") (name "unconnected-(SV3-Pad26)") (class "Default")
      (node (ref "SV3") (pin "26") (pinfunction "26_26") (pintype "passive"))
    )
    (net (code "122") (name "unconnected-(SV3-Pad33)") (class "Default")
      (node (ref "SV3") (pin "33") (pinfunction "33_33") (pintype "passive"))
    )
    (net (code "123") (name "unconnected-(SV3-Pad34)") (class "Default")
      (node (ref "SV3") (pin "34") (pinfunction "34_34") (pintype "passive"))
    )
    (net (code "124") (name "unconnected-(SV3-Pad35)") (class "Default")
      (node (ref "SV3") (pin "35") (pinfunction "35_35") (pintype "passive"))
    )
    (net (code "125") (name "unconnected-(SV3-Pad36)") (class "Default")
      (node (ref "SV3") (pin "36") (pinfunction "36_36") (pintype "passive"))
    )
    (net (code "126") (name "unconnected-(SV3-Pad37)") (class "Default")
      (node (ref "SV3") (pin "37") (pinfunction "37_37") (pintype "passive"))
    )
    (net (code "127") (name "unconnected-(SV3-Pad38)") (class "Default")
      (node (ref "SV3") (pin "38") (pinfunction "38_38") (pintype "passive"))
    )
    (net (code "128") (name "unconnected-(SV3-Pad39)") (class "Default")
      (node (ref "SV3") (pin "39") (pinfunction "39_39") (pintype "passive"))
    )
    (net (code "129") (name "unconnected-(SV3-Pad40)") (class "Default")
      (node (ref "SV3") (pin "40") (pinfunction "40_40") (pintype "passive"))
    )
    (net (code "130") (name "unconnected-(X1-Pad1)") (class "Default")
      (node (ref "X1") (pin "1") (pinfunction "1_1") (pintype "passive"))
    )
  )
)
